# pca20017_sensors.net
KiCad netlist of a schematic drawn in Altium Designer
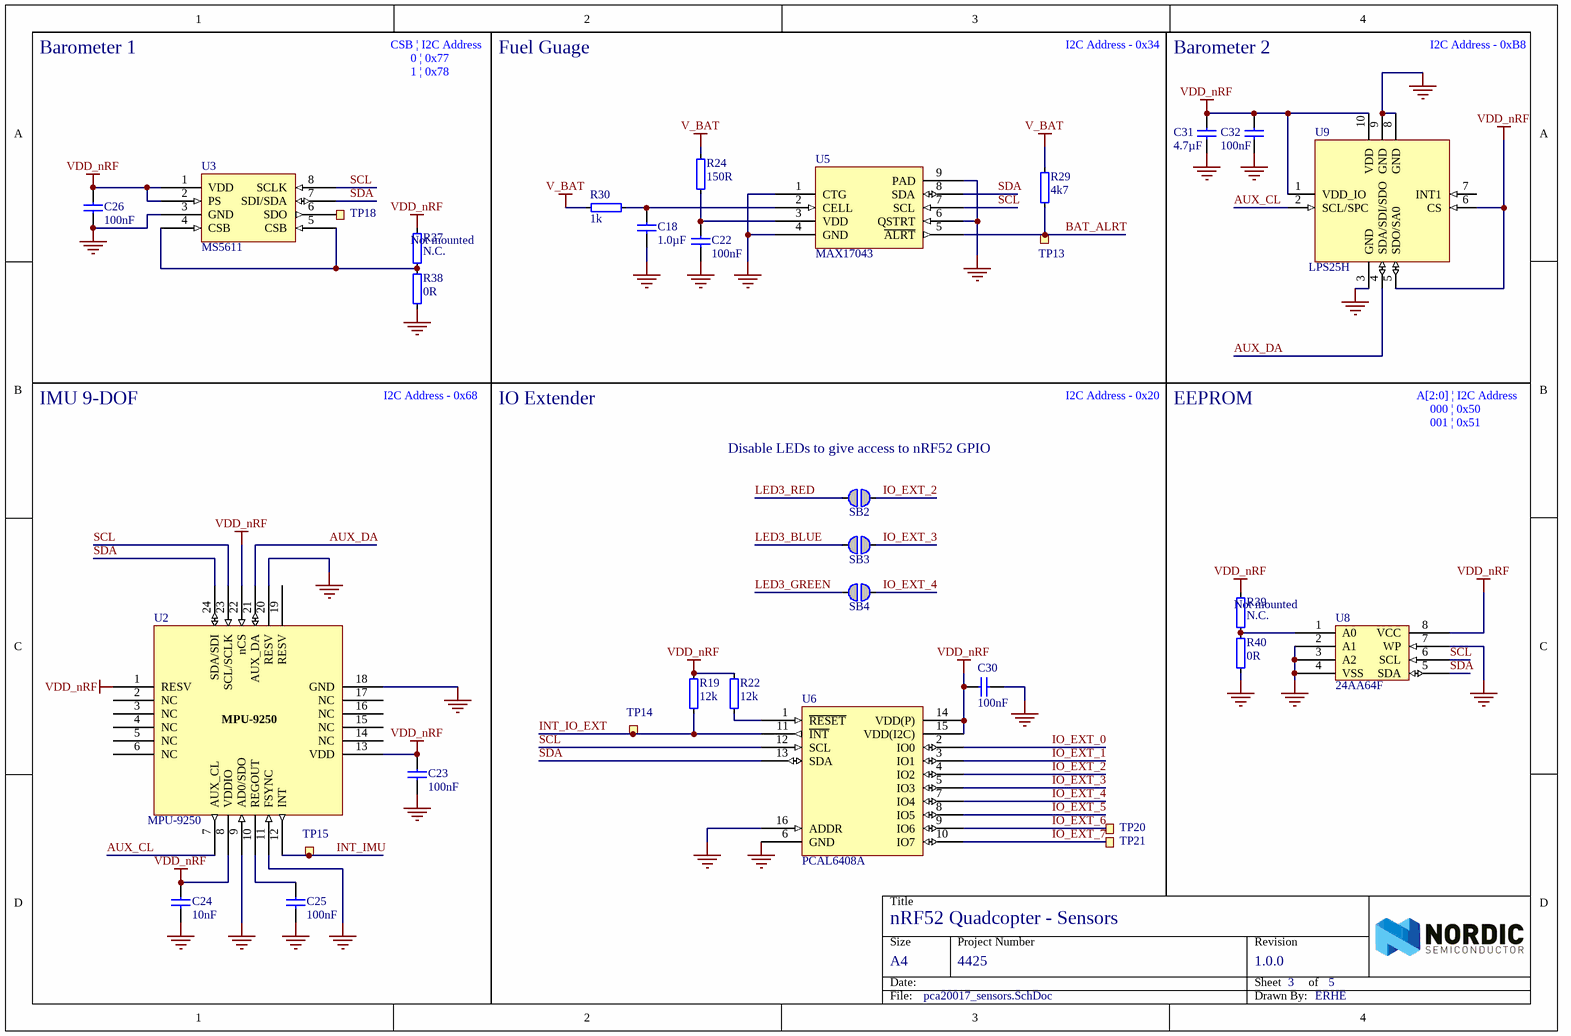
[diagram p0: pca20017_sensors.SchDoc]

(export (version "E")
  (design (tool "Eeschema 10.0.6"))
  (components
    (comp (ref "C18")
      (value "1.0µF")
      (footprint "CAPC1005X04L")
      (description "Capacitor, X5R, ±5%")
      (fields (field (name "PART NUMBER") "C0402-1µ0") (field (name "PUBLISHER") "Nordic Semiconductor"))
      (libsource (lib "Nordic Passive DB") (part "CAP"))
    )
    (comp (ref "C22")
      (value "100nF")
      (footprint "CAPC1005X04L")
      (description "Capacitor, X7R, ±10%")
      (fields (field (name "PART NUMBER") "C0402-100n") (field (name "PUBLISHER") "Nordic Semiconductor"))
      (libsource (lib "Nordic Passive DB") (part "CAP"))
    )
    (comp (ref "C23")
      (value "100nF")
      (footprint "CAPC1005X04L")
      (description "Capacitor, X7R, ±10%")
      (fields (field (name "PART NUMBER") "C0402-100n") (field (name "PUBLISHER") "Nordic Semiconductor"))
      (libsource (lib "Nordic Passive DB") (part "CAP"))
    )
    (comp (ref "C24")
      (value "10nF")
      (footprint "CAPC1005X04L")
      (description "Capacitor, X7R, ±10%")
      (fields (field (name "PART NUMBER") "C0402-10n") (field (name "PUBLISHER") "Nordic Semiconductor"))
      (libsource (lib "Nordic Passive DB") (part "CAP"))
    )
    (comp (ref "C25")
      (value "100nF")
      (footprint "CAPC1005X04L")
      (description "Capacitor, X7R, ±10%")
      (fields (field (name "PART NUMBER") "C0402-100n") (field (name "PUBLISHER") "Nordic Semiconductor"))
      (libsource (lib "Nordic Passive DB") (part "CAP"))
    )
    (comp (ref "C26")
      (value "100nF")
      (footprint "CAPC1005X04L")
      (description "Capacitor, X7R, ±10%")
      (fields (field (name "PART NUMBER") "C0402-100n") (field (name "PUBLISHER") "Nordic Semiconductor"))
      (libsource (lib "Nordic Passive DB") (part "CAP"))
    )
    (comp (ref "C30")
      (value "100nF")
      (footprint "CAPC1005X04L")
      (description "Capacitor, X7R, ±10%")
      (fields (field (name "PART NUMBER") "C0402-100n") (field (name "PUBLISHER") "Nordic Semiconductor"))
      (libsource (lib "Nordic Passive DB") (part "CAP"))
    )
    (comp (ref "C31")
      (value "4.7µF")
      (footprint "CAPC1608X06L")
      (description "Capacitor, X5R, ±10%")
      (fields (field (name "PART NUMBER") "C0603-4µ7") (field (name "PUBLISHER") "Nordic Semiconductor"))
      (libsource (lib "Nordic Passive DB") (part "CAP"))
    )
    (comp (ref "C32")
      (value "100nF")
      (footprint "CAPC1005X04L")
      (description "Capacitor, X7R, ±10%")
      (fields (field (name "PART NUMBER") "C0402-100n") (field (name "PUBLISHER") "Nordic Semiconductor"))
      (libsource (lib "Nordic Passive DB") (part "CAP"))
    )
    (comp (ref "R19")
      (value "12k")
      (footprint "RESC1005X04L")
      (description "Resistor, ±1%, 0.063W")
      (fields (field (name "PART NUMBER") "R0402-12k") (field (name "PUBLISHER") "Nordic Semiconductor"))
      (libsource (lib "Nordic Passive DB") (part "RES_1"))
    )
    (comp (ref "R22")
      (value "12k")
      (footprint "RESC1005X04L")
      (description "Resistor, ±1%, 0.063W")
      (fields (field (name "PART NUMBER") "R0402-12k") (field (name "PUBLISHER") "Nordic Semiconductor"))
      (libsource (lib "Nordic Passive DB") (part "RES_1"))
    )
    (comp (ref "R24")
      (value "150R")
      (footprint "RESC1005X04L")
      (description "Resistor, ±1%, 0.063W")
      (fields (field (name "PART NUMBER") "R0402-150") (field (name "PUBLISHER") "Nordic Semiconductor"))
      (libsource (lib "Nordic Passive DB") (part "RES_1"))
    )
    (comp (ref "R29")
      (value "4k7")
      (footprint "RESC1005X04L")
      (description "Resistor, ±1%, 0.063W")
      (fields (field (name "PART NUMBER") "R0402-4k7") (field (name "PUBLISHER") "Nordic Semiconductor"))
      (libsource (lib "Nordic Passive DB") (part "RES_1"))
    )
    (comp (ref "R30")
      (value "1k")
      (footprint "RESC1005X04L")
      (description "Resistor, ±1%, 0.063W")
      (fields (field (name "PART NUMBER") "R0402-1k0") (field (name "PUBLISHER") "Nordic Semiconductor"))
      (libsource (lib "Nordic Passive DB") (part "RES_1"))
    )
    (comp (ref "R37")
      (value "N.C.")
      (footprint "RESC1005X04L")
      (description "Not mounted")
      (fields
        (field (name "PART NUMBER") "R0402-N.C.")
        (field (name "ASSEMBLY") "Not mounted")
        (field (name "PUBLISHER") "Nordic Semiconductor")
      )
      (libsource (lib "Nordic Passive DB") (part "RES_1"))
    )
    (comp (ref "R38")
      (value "0R")
      (footprint "RESC1005X04L")
      (description "Resistor, ±5%, 0.063W")
      (fields (field (name "PART NUMBER") "R0402-0R") (field (name "PUBLISHER") "Nordic Semiconductor"))
      (libsource (lib "Nordic Passive DB") (part "RES_1"))
    )
    (comp (ref "R39")
      (value "N.C.")
      (footprint "RESC1005X04L")
      (description "Not mounted")
      (fields
        (field (name "PART NUMBER") "R0402-N.C.")
        (field (name "ASSEMBLY") "Not mounted")
        (field (name "PUBLISHER") "Nordic Semiconductor")
      )
      (libsource (lib "Nordic Passive DB") (part "RES_1"))
    )
    (comp (ref "R40")
      (value "0R")
      (footprint "RESC1005X04L")
      (description "Resistor, ±5%, 0.063W")
      (fields (field (name "PART NUMBER") "R0402-0R") (field (name "PUBLISHER") "Nordic Semiconductor"))
      (libsource (lib "Nordic Passive DB") (part "RES_1"))
    )
    (comp (ref "SB2")
      (value "Solderbridge")
      (footprint "Solderbridge")
      (fields (field (name "PUBLISHER") "Nordic Semiconductor"))
      (libsource (lib "Nordic Passive DB") (part "SOLDERBRIDGE"))
    )
    (comp (ref "SB3")
      (value "Solderbridge")
      (footprint "Solderbridge")
      (fields (field (name "PUBLISHER") "Nordic Semiconductor"))
      (libsource (lib "Nordic Passive DB") (part "SOLDERBRIDGE"))
    )
    (comp (ref "SB4")
      (value "Solderbridge")
      (footprint "Solderbridge")
      (fields (field (name "PUBLISHER") "Nordic Semiconductor"))
      (libsource (lib "Nordic Passive DB") (part "SOLDERBRIDGE"))
    )
    (comp (ref "TP13")
      (value "Ø1.0mm,SMD")
      (footprint "TP_SMD_Ø1.0mm")
      (description "1.0mm circular SMD testpad")
      (fields
        (field (name "PART NUMBER") "TP_SMD_Ø1.0MM")
        (field (name "MANUFACTURER") "Nordic Semiconductor")
        (field (name "PUBLISHER") "Nordic Semiconductor")
      )
      (libsource (lib "Nordic Passive DB") (part "TESTPAD"))
    )
    (comp (ref "TP14")
      (value "Ø1.0mm,SMD")
      (footprint "TP_SMD_Ø1.0mm")
      (description "1.0mm circular SMD testpad")
      (fields
        (field (name "PART NUMBER") "TP_SMD_Ø1.0MM")
        (field (name "MANUFACTURER") "Nordic Semiconductor")
        (field (name "PUBLISHER") "Nordic Semiconductor")
      )
      (libsource (lib "") (part "TESTPAD_1"))
    )
    (comp (ref "TP15")
      (value "Ø1.0mm,SMD")
      (footprint "TP_SMD_Ø1.0mm")
      (description "1.0mm circular SMD testpad")
      (fields
        (field (name "PART NUMBER") "TP_SMD_Ø1.0MM")
        (field (name "MANUFACTURER") "Nordic Semiconductor")
        (field (name "PUBLISHER") "Nordic Semiconductor")
      )
      (libsource (lib "") (part "TESTPAD_1"))
    )
    (comp (ref "TP18")
      (value "Ø1.0mm,SMD")
      (footprint "TP_SMD_Ø1.0mm")
      (description "1.0mm circular SMD testpad")
      (fields
        (field (name "PART NUMBER") "TP_SMD_Ø1.0MM")
        (field (name "MANUFACTURER") "Nordic Semiconductor")
        (field (name "PUBLISHER") "Nordic Semiconductor")
      )
      (libsource (lib "") (part "TESTPAD_2"))
    )
    (comp (ref "TP20")
      (value "Ø1.0mm,SMD")
      (footprint "TP_SMD_Ø1.0mm")
      (description "1.0mm circular SMD testpad")
      (fields
        (field (name "PART NUMBER") "TP_SMD_Ø1.0MM")
        (field (name "MANUFACTURER") "Nordic Semiconductor")
        (field (name "PUBLISHER") "Nordic Semiconductor")
      )
      (libsource (lib "") (part "TESTPAD_2"))
    )
    (comp (ref "TP21")
      (value "Ø1.0mm,SMD")
      (footprint "TP_SMD_Ø1.0mm")
      (description "1.0mm circular SMD testpad")
      (fields
        (field (name "PART NUMBER") "TP_SMD_Ø1.0MM")
        (field (name "MANUFACTURER") "Nordic Semiconductor")
        (field (name "PUBLISHER") "Nordic Semiconductor")
      )
      (libsource (lib "") (part "TESTPAD_2"))
    )
    (comp (ref "U2")
      (value "MPU-9250")
      (footprint "QFN40P300X300X105_HS-25N")
      (description "9-axis MotionTracking™ Device")
      (fields (field (name "MANUFACTURER") "InvenSense") (field (name "PUBLISHER") "Nordic Semiconductor"))
      (libsource (lib "Nordic Active DB") (part "MPU-9250"))
    )
    (comp (ref "U3")
      (value "MS5611")
      (footprint "QFN125P300X500X100-8N")
      (description "Accurate Pressure/Altitude and Temperature sensor with I2C and SPI interface")
      (fields
        (field (name "PART NUMBER") "MS5611-01BA03")
        (field (name "MANUFACTURER") "Measurement Specialties")
        (field (name "PUBLISHER") "Nordic Semiconductor")
      )
      (libsource (lib "Nordic Active DB") (part "MS5611-01BA03"))
    )
    (comp (ref "U5")
      (value "MAX17043")
      (footprint "MAX17043")
      (description "IC FUEL FUAGE LI-ION")
      (fields
        (field (name "MANUFACTURER") "Maxim")
        (field (name "MANUFACTURER PART NUMBER") "MAX17043G+U")
        (field (name "PUBLISHER") "Nordic Semiconductor")
      )
      (libsource (lib "Nordic Active DB") (part "MAX17043"))
    )
    (comp (ref "U6")
      (value "PCAL6408A")
      (footprint "XQFN40P180X260X50-16N")
      (description "8-bit I2C-bus I/O expander with interrupt output")
      (fields
        (field (name "PART NUMBER") "PCAL6408AHK")
        (field (name "MANUFACTURER") "NXP Semiconductors")
        (field (name "PUBLISHER") "Nordic Semiconductor")
      )
      (libsource (lib "Nordic Active DB") (part "PCAL6408AHK"))
    )
    (comp (ref "U8")
      (value "24AA64F")
      (footprint "24AA64F")
      (description "IC EEPROM 64K with I2C interface TDFN-8")
      (fields
        (field (name "MANUFACTURER") "Microchip")
        (field (name "MANUFACTURER PART NUMBER") "24AA64T-I/MNY")
        (field (name "PUBLISHER") "Nordic Semiconductor")
      )
      (libsource (lib "Nordic Active DB") (part "24AA64F"))
    )
    (comp (ref "U9")
      (value "LPS25H")
      (footprint "HCLGA-10L (2.5x2.5x1.0mm)")
      (description "MEMS pressure sensor: 260-1260 hPa absolute digital output barometer")
      (fields
        (field (name "PART NUMBER") "LPS25H (NRND)")
        (field (name "MANUFACTURER") "STMicroelectronics")
        (field (name "PUBLISHER") "Nordic Semiconductor")
      )
      (libsource (lib "Nordic Active DB") (part "LPS25H"))
    )
  )
  (nets
    (net (code "1") (name "/AUX_CL") (class "Default")
      (node (ref "U2") (pin "7") (pinfunction "AUX_CL_7") (pintype "output"))
      (node (ref "U9") (pin "2") (pinfunction "SCL/SPC_2") (pintype "input"))
    )
    (net (code "2") (name "/AUX_DA") (class "Default")
      (node (ref "U2") (pin "21") (pinfunction "AUX_DA_21") (pintype "bidirectional"))
      (node (ref "U9") (pin "4") (pinfunction "SDA/SDI/SDO_4") (pintype "bidirectional"))
    )
    (net (code "3") (name "/BAT_ALRT") (class "Default")
      (node (ref "R29") (pin "1") (pinfunction "1_1") (pintype "passive"))
      (node (ref "TP13") (pin "1") (pinfunction "1_1") (pintype "passive"))
      (node (ref "U5") (pin "5") (pinfunction "~{ALRT}_5") (pintype "output"))
    )
    (net (code "4") (name "/INT_IMU") (class "Default")
      (node (ref "TP15") (pin "1") (pinfunction "1_1") (pintype "passive"))
      (node (ref "U2") (pin "12") (pinfunction "INT_12") (pintype "output"))
    )
    (net (code "5") (name "/INT_IO_EXT") (class "Default")
      (node (ref "R19") (pin "1") (pinfunction "1_1") (pintype "passive"))
      (node (ref "TP14") (pin "1") (pinfunction "1_1") (pintype "passive"))
      (node (ref "U6") (pin "11") (pinfunction "~{INT}_11") (pintype "output"))
    )
    (net (code "6") (name "/IO_EXT_0") (class "Default")
      (node (ref "U6") (pin "2") (pinfunction "IO0_2") (pintype "bidirectional"))
    )
    (net (code "7") (name "/IO_EXT_1") (class "Default")
      (node (ref "U6") (pin "3") (pinfunction "IO1_3") (pintype "bidirectional"))
    )
    (net (code "8") (name "/IO_EXT_2") (class "Default")
      (node (ref "SB2") (pin "2") (pinfunction "1_2") (pintype "passive"))
      (node (ref "U6") (pin "4") (pinfunction "IO2_4") (pintype "bidirectional"))
    )
    (net (code "9") (name "/IO_EXT_3") (class "Default")
      (node (ref "SB3") (pin "2") (pinfunction "1_2") (pintype "passive"))
      (node (ref "U6") (pin "5") (pinfunction "IO3_5") (pintype "bidirectional"))
    )
    (net (code "10") (name "/IO_EXT_4") (class "Default")
      (node (ref "SB4") (pin "2") (pinfunction "1_2") (pintype "passive"))
      (node (ref "U6") (pin "7") (pinfunction "IO4_7") (pintype "bidirectional"))
    )
    (net (code "11") (name "/IO_EXT_5") (class "Default")
      (node (ref "U6") (pin "8") (pinfunction "IO5_8") (pintype "bidirectional"))
    )
    (net (code "12") (name "/IO_EXT_6") (class "Default")
      (node (ref "TP20") (pin "1") (pinfunction "1_1") (pintype "passive"))
      (node (ref "U6") (pin "9") (pinfunction "IO6_9") (pintype "bidirectional"))
    )
    (net (code "13") (name "/IO_EXT_7") (class "Default")
      (node (ref "TP21") (pin "1") (pinfunction "1_1") (pintype "passive"))
      (node (ref "U6") (pin "10") (pinfunction "IO7_10") (pintype "bidirectional"))
    )
    (net (code "14") (name "/LED3_BLUE") (class "Default")
      (node (ref "SB3") (pin "1") (pinfunction "0_1") (pintype "passive"))
    )
    (net (code "15") (name "/LED3_GREEN") (class "Default")
      (node (ref "SB4") (pin "1") (pinfunction "0_1") (pintype "passive"))
    )
    (net (code "16") (name "/LED3_RED") (class "Default")
      (node (ref "SB2") (pin "1") (pinfunction "0_1") (pintype "passive"))
    )
    (net (code "17") (name "/SCL") (class "Default")
      (node (ref "U2") (pin "23") (pinfunction "SCL/SCLK_23") (pintype "input"))
      (node (ref "U3") (pin "8") (pinfunction "SCLK_8") (pintype "input"))
      (node (ref "U5") (pin "7") (pinfunction "SCL_7") (pintype "input"))
      (node (ref "U6") (pin "12") (pinfunction "SCL_12") (pintype "input"))
      (node (ref "U8") (pin "6") (pinfunction "SCL_6") (pintype "input"))
    )
    (net (code "18") (name "/SDA") (class "Default")
      (node (ref "U2") (pin "24") (pinfunction "SDA/SDI_24") (pintype "bidirectional"))
      (node (ref "U3") (pin "7") (pinfunction "SDI/SDA_7") (pintype "bidirectional"))
      (node (ref "U5") (pin "8") (pinfunction "SDA_8") (pintype "bidirectional"))
      (node (ref "U6") (pin "13") (pinfunction "SDA_13") (pintype "bidirectional"))
      (node (ref "U8") (pin "5") (pinfunction "SDA_5") (pintype "bidirectional"))
    )
    (net (code "19") (name "GND") (class "Default")
      (node (ref "C18") (pin "1") (pinfunction "1_1") (pintype "passive"))
      (node (ref "C22") (pin "1") (pinfunction "1_1") (pintype "passive"))
      (node (ref "C23") (pin "1") (pinfunction "1_1") (pintype "passive"))
      (node (ref "C24") (pin "1") (pinfunction "1_1") (pintype "passive"))
      (node (ref "C25") (pin "1") (pinfunction "1_1") (pintype "passive"))
      (node (ref "C26") (pin "2") (pinfunction "2_2") (pintype "passive"))
      (node (ref "C30") (pin "1") (pinfunction "1_1") (pintype "passive"))
      (node (ref "C31") (pin "1") (pinfunction "1_1") (pintype "passive"))
      (node (ref "C32") (pin "1") (pinfunction "1_1") (pintype "passive"))
      (node (ref "R38") (pin "1") (pinfunction "1_1") (pintype "passive"))
      (node (ref "R40") (pin "1") (pinfunction "1_1") (pintype "passive"))
      (node (ref "U2") (pin "11") (pinfunction "FSYNC_11") (pintype "input"))
      (node (ref "U2") (pin "18") (pinfunction "GND_18") (pintype "power_in"))
      (node (ref "U2") (pin "20") (pinfunction "RESV_20") (pintype "passive"))
      (node (ref "U2") (pin "9") (pinfunction "AD0/SDO_9") (pintype "input"))
      (node (ref "U3") (pin "3") (pinfunction "GND_3") (pintype "power_in"))
      (node (ref "U5") (pin "1") (pinfunction "CTG_1") (pintype "passive"))
      (node (ref "U5") (pin "4") (pinfunction "GND_4") (pintype "power_in"))
      (node (ref "U5") (pin "6") (pinfunction "QSTRT_6") (pintype "input"))
      (node (ref "U5") (pin "9") (pinfunction "PAD_9") (pintype "power_in"))
      (node (ref "U6") (pin "16") (pinfunction "ADDR_16") (pintype "input"))
      (node (ref "U6") (pin "6") (pinfunction "GND_6") (pintype "power_in"))
      (node (ref "U8") (pin "2") (pinfunction "A1_2") (pintype "passive"))
      (node (ref "U8") (pin "3") (pinfunction "A2_3") (pintype "passive"))
      (node (ref "U8") (pin "4") (pinfunction "VSS_4") (pintype "power_in"))
      (node (ref "U8") (pin "7") (pinfunction "WP_7") (pintype "input"))
      (node (ref "U9") (pin "3") (pinfunction "GND_3") (pintype "power_in"))
      (node (ref "U9") (pin "8") (pinfunction "GND_8") (pintype "power_in"))
      (node (ref "U9") (pin "9") (pinfunction "GND_9") (pintype "power_in"))
    )
    (net (code "20") (name "Net-(R37-Pad1)") (class "Default")
      (node (ref "R37") (pin "1") (pinfunction "1_1") (pintype "passive"))
      (node (ref "R38") (pin "2") (pinfunction "2_2") (pintype "passive"))
      (node (ref "U3") (pin "4") (pinfunction "CSB_4") (pintype "input"))
      (node (ref "U3") (pin "5") (pinfunction "CSB_5") (pintype "input"))
    )
    (net (code "21") (name "Net-(U2-REGOUT)") (class "Default")
      (node (ref "C25") (pin "2") (pinfunction "2_2") (pintype "passive"))
      (node (ref "U2") (pin "10") (pinfunction "REGOUT_10") (pintype "passive"))
    )
    (net (code "22") (name "Net-(U3-SDO)") (class "Default")
      (node (ref "TP18") (pin "1") (pinfunction "1_1") (pintype "passive"))
      (node (ref "U3") (pin "6") (pinfunction "SDO_6") (pintype "output"))
    )
    (net (code "23") (name "Net-(U5-CELL)") (class "Default")
      (node (ref "C18") (pin "2") (pinfunction "2_2") (pintype "passive"))
      (node (ref "R30") (pin "2") (pinfunction "2_2") (pintype "passive"))
      (node (ref "U5") (pin "2") (pinfunction "CELL_2") (pintype "input"))
    )
    (net (code "24") (name "Net-(U5-VDD)") (class "Default")
      (node (ref "C22") (pin "2") (pinfunction "2_2") (pintype "passive"))
      (node (ref "R24") (pin "1") (pinfunction "1_1") (pintype "passive"))
      (node (ref "U5") (pin "3") (pinfunction "VDD_3") (pintype "power_in"))
    )
    (net (code "25") (name "Net-(U6-~{RESET})") (class "Default")
      (node (ref "R22") (pin "1") (pinfunction "1_1") (pintype "passive"))
      (node (ref "U6") (pin "1") (pinfunction "~{RESET}_1") (pintype "input"))
    )
    (net (code "26") (name "Net-(U8-A0)") (class "Default")
      (node (ref "R39") (pin "1") (pinfunction "1_1") (pintype "passive"))
      (node (ref "R40") (pin "2") (pinfunction "2_2") (pintype "passive"))
      (node (ref "U8") (pin "1") (pinfunction "A0_1") (pintype "passive"))
    )
    (net (code "27") (name "VDD_nRF") (class "Default")
      (node (ref "C23") (pin "2") (pinfunction "2_2") (pintype "passive"))
      (node (ref "C24") (pin "2") (pinfunction "2_2") (pintype "passive"))
      (node (ref "C26") (pin "1") (pinfunction "1_1") (pintype "passive"))
      (node (ref "C30") (pin "2") (pinfunction "2_2") (pintype "passive"))
      (node (ref "C31") (pin "2") (pinfunction "2_2") (pintype "passive"))
      (node (ref "C32") (pin "2") (pinfunction "2_2") (pintype "passive"))
      (node (ref "R19") (pin "2") (pinfunction "2_2") (pintype "passive"))
      (node (ref "R22") (pin "2") (pinfunction "2_2") (pintype "passive"))
      (node (ref "R37") (pin "2") (pinfunction "2_2") (pintype "passive"))
      (node (ref "R39") (pin "2") (pinfunction "2_2") (pintype "passive"))
      (node (ref "U2") (pin "1") (pinfunction "RESV_1") (pintype "passive"))
      (node (ref "U2") (pin "13") (pinfunction "VDD_13") (pintype "power_in"))
      (node (ref "U2") (pin "22") (pinfunction "nCS_22") (pintype "input"))
      (node (ref "U2") (pin "8") (pinfunction "VDDIO_8") (pintype "power_in"))
      (node (ref "U3") (pin "1") (pinfunction "VDD_1") (pintype "power_in"))
      (node (ref "U3") (pin "2") (pinfunction "PS_2") (pintype "input"))
      (node (ref "U6") (pin "14") (pinfunction "VDD(P)_14") (pintype "power_in"))
      (node (ref "U6") (pin "15") (pinfunction "VDD(I2C)_15") (pintype "power_in"))
      (node (ref "U8") (pin "8") (pinfunction "VCC_8") (pintype "power_in"))
      (node (ref "U9") (pin "1") (pinfunction "VDD_IO_1") (pintype "power_in"))
      (node (ref "U9") (pin "10") (pinfunction "VDD_10") (pintype "power_in"))
      (node (ref "U9") (pin "5") (pinfunction "SDO/SA0_5") (pintype "bidirectional"))
      (node (ref "U9") (pin "6") (pinfunction "CS_6") (pintype "input"))
    )
    (net (code "28") (name "V_BAT") (class "Default")
      (node (ref "R24") (pin "2") (pinfunction "2_2") (pintype "passive"))
      (node (ref "R29") (pin "2") (pinfunction "2_2") (pintype "passive"))
      (node (ref "R30") (pin "1") (pinfunction "1_1") (pintype "passive"))
    )
    (net (code "29") (name "unconnected-(U2-NC-Pad2)") (class "Default")
      (node (ref "U2") (pin "2") (pinfunction "NC_2") (pintype "passive"))
    )
    (net (code "30") (name "unconnected-(U2-NC-Pad3)") (class "Default")
      (node (ref "U2") (pin "3") (pinfunction "NC_3") (pintype "passive"))
    )
    (net (code "31") (name "unconnected-(U2-NC-Pad4)") (class "Default")
      (node (ref "U2") (pin "4") (pinfunction "NC_4") (pintype "passive"))
    )
    (net (code "32") (name "unconnected-(U2-NC-Pad5)") (class "Default")
      (node (ref "U2") (pin "5") (pinfunction "NC_5") (pintype "passive"))
    )
    (net (code "33") (name "unconnected-(U2-NC-Pad6)") (class "Default")
      (node (ref "U2") (pin "6") (pinfunction "NC_6") (pintype "passive"))
    )
    (net (code "34") (name "unconnected-(U2-NC-Pad14)") (class "Default")
      (node (ref "U2") (pin "14") (pinfunction "NC_14") (pintype "passive"))
    )
    (net (code "35") (name "unconnected-(U2-NC-Pad15)") (class "Default")
      (node (ref "U2") (pin "15") (pinfunction "NC_15") (pintype "passive"))
    )
    (net (code "36") (name "unconnected-(U2-NC-Pad16)") (class "Default")
      (node (ref "U2") (pin "16") (pinfunction "NC_16") (pintype "passive"))
    )
    (net (code "37") (name "unconnected-(U2-NC-Pad17)") (class "Default")
      (node (ref "U2") (pin "17") (pinfunction "NC_17") (pintype "passive"))
    )
    (net (code "38") (name "unconnected-(U2-RESV-Pad19)") (class "Default")
      (node (ref "U2") (pin "19") (pinfunction "RESV_19") (pintype "passive"))
    )
    (net (code "39") (name "unconnected-(U9-INT1-Pad7)") (class "Default")
      (node (ref "U9") (pin "7") (pinfunction "INT1_7") (pintype "input"))
    )
  )
)
